# Sheet3.net
KiCad netlist of a schematic drawn in Altium Designer
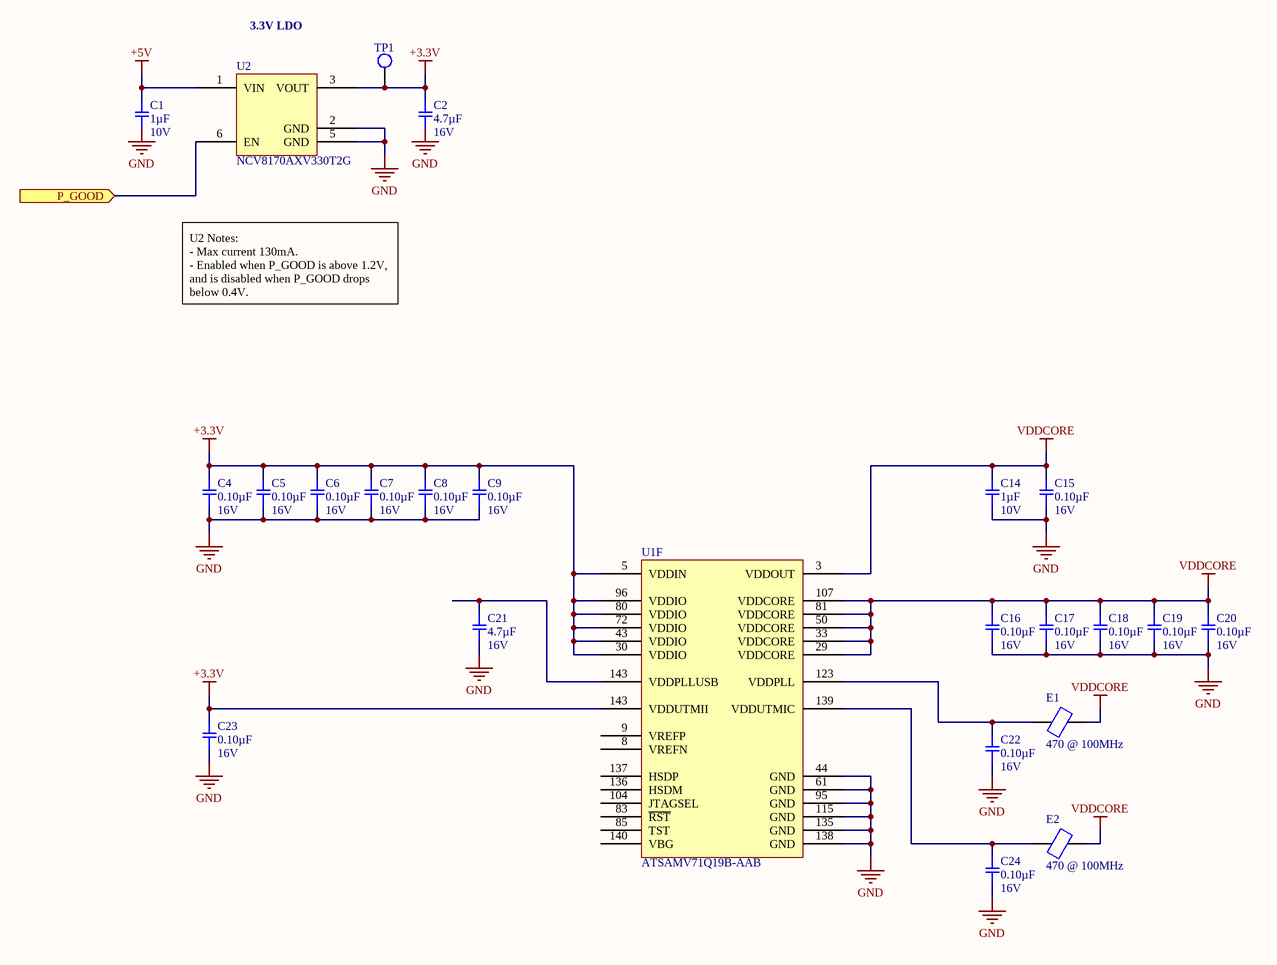
[diagram p0: Sheet3.SchDoc]

(export (version "E")
  (design (tool "Eeschema 10.0.6"))
  (components
    (comp (ref "C1")
      (value "1µF")
      (footprint "SMD-0402C")
      (description "CAP CER 1UF 10V X7S 0402")
      (fields
        (field (name "DIGI-KEY PART NUMBER") "490-13409-1-ND")
        (field (name "PART NUMBER") "GCM155C71A105KE38D")
        (field (name "VOLTAGE") "10V")
      )
      (libsource (lib "capacitor_murata_0402") (part "GCM155C71A105KE38D"))
    )
    (comp (ref "C2")
      (value "4.7µF")
      (footprint "SMD-0805C")
      (description "CAP CER 4.7UF 16V X7R 0805")
      (fields
        (field (name "DIGI-KEY PART NUMBER") "490-10557-1-ND")
        (field (name "PART NUMBER") "GCJ21BR71C475KA01L")
        (field (name "VOLTAGE") "16V")
      )
      (libsource (lib "capacitor_murata_0805") (part "GCJ21BR71C475KA01L"))
    )
    (comp (ref "C4")
      (value "0.10µF")
      (footprint "SMD-0402C")
      (description "CAP CER 0.1UF 16V X7R 0402")
      (fields
        (field (name "DIGI-KEY PART NUMBER") "490-4759-1-ND")
        (field (name "PART NUMBER") "GCM155R71C104KA55D")
        (field (name "VOLTAGE") "16V")
      )
      (libsource (lib "capacitor_murata_0402") (part "GCM155R71C104KA55D"))
    )
    (comp (ref "C5")
      (value "0.10µF")
      (footprint "SMD-0402C")
      (description "CAP CER 0.1UF 16V X7R 0402")
      (fields
        (field (name "DIGI-KEY PART NUMBER") "490-4759-1-ND")
        (field (name "PART NUMBER") "GCM155R71C104KA55D")
        (field (name "VOLTAGE") "16V")
      )
      (libsource (lib "capacitor_murata_0402") (part "GCM155R71C104KA55D"))
    )
    (comp (ref "C6")
      (value "0.10µF")
      (footprint "SMD-0402C")
      (description "CAP CER 0.1UF 16V X7R 0402")
      (fields
        (field (name "DIGI-KEY PART NUMBER") "490-4759-1-ND")
        (field (name "PART NUMBER") "GCM155R71C104KA55D")
        (field (name "VOLTAGE") "16V")
      )
      (libsource (lib "capacitor_murata_0402") (part "GCM155R71C104KA55D"))
    )
    (comp (ref "C7")
      (value "0.10µF")
      (footprint "SMD-0402C")
      (description "CAP CER 0.1UF 16V X7R 0402")
      (fields
        (field (name "DIGI-KEY PART NUMBER") "490-4759-1-ND")
        (field (name "PART NUMBER") "GCM155R71C104KA55D")
        (field (name "VOLTAGE") "16V")
      )
      (libsource (lib "capacitor_murata_0402") (part "GCM155R71C104KA55D"))
    )
    (comp (ref "C8")
      (value "0.10µF")
      (footprint "SMD-0402C")
      (description "CAP CER 0.1UF 16V X7R 0402")
      (fields
        (field (name "DIGI-KEY PART NUMBER") "490-4759-1-ND")
        (field (name "PART NUMBER") "GCM155R71C104KA55D")
        (field (name "VOLTAGE") "16V")
      )
      (libsource (lib "capacitor_murata_0402") (part "GCM155R71C104KA55D"))
    )
    (comp (ref "C9")
      (value "0.10µF")
      (footprint "SMD-0402C")
      (description "CAP CER 0.1UF 16V X7R 0402")
      (fields
        (field (name "DIGI-KEY PART NUMBER") "490-4759-1-ND")
        (field (name "PART NUMBER") "GCM155R71C104KA55D")
        (field (name "VOLTAGE") "16V")
      )
      (libsource (lib "capacitor_murata_0402") (part "GCM155R71C104KA55D"))
    )
    (comp (ref "C14")
      (value "1µF")
      (footprint "SMD-0402C")
      (description "CAP CER 1UF 10V X7S 0402")
      (fields
        (field (name "DIGI-KEY PART NUMBER") "490-13409-1-ND")
        (field (name "PART NUMBER") "GCM155C71A105KE38D")
        (field (name "VOLTAGE") "10V")
      )
      (libsource (lib "capacitor_murata_0402") (part "GCM155C71A105KE38D"))
    )
    (comp (ref "C15")
      (value "0.10µF")
      (footprint "SMD-0402C")
      (description "CAP CER 0.1UF 16V X7R 0402")
      (fields
        (field (name "DIGI-KEY PART NUMBER") "490-4759-1-ND")
        (field (name "PART NUMBER") "GCM155R71C104KA55D")
        (field (name "VOLTAGE") "16V")
      )
      (libsource (lib "capacitor_murata_0402") (part "GCM155R71C104KA55D"))
    )
    (comp (ref "C16")
      (value "0.10µF")
      (footprint "SMD-0402C")
      (description "CAP CER 0.1UF 16V X7R 0402")
      (fields
        (field (name "DIGI-KEY PART NUMBER") "490-4759-1-ND")
        (field (name "PART NUMBER") "GCM155R71C104KA55D")
        (field (name "VOLTAGE") "16V")
      )
      (libsource (lib "capacitor_murata_0402") (part "GCM155R71C104KA55D"))
    )
    (comp (ref "C17")
      (value "0.10µF")
      (footprint "SMD-0402C")
      (description "CAP CER 0.1UF 16V X7R 0402")
      (fields
        (field (name "DIGI-KEY PART NUMBER") "490-4759-1-ND")
        (field (name "PART NUMBER") "GCM155R71C104KA55D")
        (field (name "VOLTAGE") "16V")
      )
      (libsource (lib "capacitor_murata_0402") (part "GCM155R71C104KA55D"))
    )
    (comp (ref "C18")
      (value "0.10µF")
      (footprint "SMD-0402C")
      (description "CAP CER 0.1UF 16V X7R 0402")
      (fields
        (field (name "DIGI-KEY PART NUMBER") "490-4759-1-ND")
        (field (name "PART NUMBER") "GCM155R71C104KA55D")
        (field (name "VOLTAGE") "16V")
      )
      (libsource (lib "capacitor_murata_0402") (part "GCM155R71C104KA55D"))
    )
    (comp (ref "C19")
      (value "0.10µF")
      (footprint "SMD-0402C")
      (description "CAP CER 0.1UF 16V X7R 0402")
      (fields
        (field (name "DIGI-KEY PART NUMBER") "490-4759-1-ND")
        (field (name "PART NUMBER") "GCM155R71C104KA55D")
        (field (name "VOLTAGE") "16V")
      )
      (libsource (lib "capacitor_murata_0402") (part "GCM155R71C104KA55D"))
    )
    (comp (ref "C20")
      (value "0.10µF")
      (footprint "SMD-0402C")
      (description "CAP CER 0.1UF 16V X7R 0402")
      (fields
        (field (name "DIGI-KEY PART NUMBER") "490-4759-1-ND")
        (field (name "PART NUMBER") "GCM155R71C104KA55D")
        (field (name "VOLTAGE") "16V")
      )
      (libsource (lib "capacitor_murata_0402") (part "GCM155R71C104KA55D"))
    )
    (comp (ref "C21")
      (value "4.7µF")
      (footprint "SMD-0805C")
      (description "CAP CER 4.7UF 16V X7R 0805")
      (fields
        (field (name "DIGI-KEY PART NUMBER") "490-10557-1-ND")
        (field (name "PART NUMBER") "GCJ21BR71C475KA01L")
        (field (name "VOLTAGE") "16V")
      )
      (libsource (lib "capacitor_murata_0805") (part "GCJ21BR71C475KA01L"))
    )
    (comp (ref "C22")
      (value "0.10µF")
      (footprint "SMD-0402C")
      (description "CAP CER 0.1UF 16V X7R 0402")
      (fields
        (field (name "DIGI-KEY PART NUMBER") "490-4759-1-ND")
        (field (name "PART NUMBER") "GCM155R71C104KA55D")
        (field (name "VOLTAGE") "16V")
      )
      (libsource (lib "capacitor_murata_0402") (part "GCM155R71C104KA55D"))
    )
    (comp (ref "C23")
      (value "0.10µF")
      (footprint "SMD-0402C")
      (description "CAP CER 0.1UF 16V X7R 0402")
      (fields
        (field (name "DIGI-KEY PART NUMBER") "490-4759-1-ND")
        (field (name "PART NUMBER") "GCM155R71C104KA55D")
        (field (name "VOLTAGE") "16V")
      )
      (libsource (lib "capacitor_murata_0402") (part "GCM155R71C104KA55D"))
    )
    (comp (ref "C24")
      (value "0.10µF")
      (footprint "SMD-0402C")
      (description "CAP CER 0.1UF 16V X7R 0402")
      (fields
        (field (name "DIGI-KEY PART NUMBER") "490-4759-1-ND")
        (field (name "PART NUMBER") "GCM155R71C104KA55D")
        (field (name "VOLTAGE") "16V")
      )
      (libsource (lib "capacitor_murata_0402") (part "GCM155R71C104KA55D"))
    )
    (comp (ref "E1")
      (value "470 @ 100MHz")
      (fields (field (name "Comment") "MPZ1608S471ATD25"))
      (libsource (lib "ModularPayload") (part "MPZ1608S471ATD25"))
    )
    (comp (ref "E2")
      (value "470 @ 100MHz")
      (fields (field (name "Comment") "MPZ1608S471ATD25"))
      (libsource (lib "ModularPayload") (part "MPZ1608S471ATD25"))
    )
    (comp (ref "TP1") (value "TP") (footprint "TP_SMD_40") (libsource (lib "TP") (part "TP")))
    (comp (ref "U1")
      (value "ATSAMV71Q19B-AAB")
      (footprint "TSQFP50P2200X2200X160-144N")
      (libsource (lib "ModularPayload") (part "ATSAMV71Q19B-AAB"))
    )
    (comp (ref "U2")
      (value "NCV8170AXV330T2G")
      (footprint "SOTFL50P160X60-6N")
      (libsource (lib "ModularPayload") (part "NCV8170AXV330T2G"))
    )
  )
  (nets
    (net (code "1") (name "+3.3V") (class "Default")
      (node (ref "C2") (pin "2") (pinfunction "2_2") (pintype "passive"))
      (node (ref "C23") (pin "2") (pinfunction "2_2") (pintype "passive"))
      (node (ref "C4") (pin "2") (pinfunction "2_2") (pintype "passive"))
      (node (ref "C5") (pin "2") (pinfunction "2_2") (pintype "passive"))
      (node (ref "C6") (pin "2") (pinfunction "2_2") (pintype "passive"))
      (node (ref "C7") (pin "2") (pinfunction "2_2") (pintype "passive"))
      (node (ref "C8") (pin "2") (pinfunction "2_2") (pintype "passive"))
      (node (ref "C9") (pin "2") (pinfunction "2_2") (pintype "passive"))
      (node (ref "TP1") (pin "1") (pintype "passive"))
      (node (ref "U1") (pin "143") (pinfunction "VDDUTMII_143") (pintype "passive"))
      (node (ref "U1") (pin "30") (pinfunction "VDDIO_30") (pintype "passive"))
      (node (ref "U1") (pin "43") (pinfunction "VDDIO_43") (pintype "passive"))
      (node (ref "U1") (pin "5") (pinfunction "VDDIN_5") (pintype "passive"))
      (node (ref "U1") (pin "72") (pinfunction "VDDIO_72") (pintype "passive"))
      (node (ref "U1") (pin "80") (pinfunction "VDDIO_80") (pintype "passive"))
      (node (ref "U1") (pin "96") (pinfunction "VDDIO_96") (pintype "passive"))
      (node (ref "U2") (pin "3") (pinfunction "VOUT_3") (pintype "passive"))
    )
    (net (code "2") (name "+5V") (class "Default")
      (node (ref "C1") (pin "2") (pinfunction "2_2") (pintype "passive"))
      (node (ref "U2") (pin "1") (pinfunction "VIN_1") (pintype "passive"))
    )
    (net (code "3") (name "/P_GOOD") (class "Default")
      (node (ref "U2") (pin "6") (pinfunction "EN_6") (pintype "passive"))
    )
    (net (code "4") (name "GND") (class "Default")
      (node (ref "C1") (pin "1") (pinfunction "1_1") (pintype "passive"))
      (node (ref "C14") (pin "1") (pinfunction "1_1") (pintype "passive"))
      (node (ref "C15") (pin "1") (pinfunction "1_1") (pintype "passive"))
      (node (ref "C16") (pin "1") (pinfunction "1_1") (pintype "passive"))
      (node (ref "C17") (pin "1") (pinfunction "1_1") (pintype "passive"))
      (node (ref "C18") (pin "1") (pinfunction "1_1") (pintype "passive"))
      (node (ref "C19") (pin "1") (pinfunction "1_1") (pintype "passive"))
      (node (ref "C2") (pin "1") (pinfunction "1_1") (pintype "passive"))
      (node (ref "C20") (pin "1") (pinfunction "1_1") (pintype "passive"))
      (node (ref "C21") (pin "1") (pinfunction "1_1") (pintype "passive"))
      (node (ref "C22") (pin "1") (pinfunction "1_1") (pintype "passive"))
      (node (ref "C23") (pin "1") (pinfunction "1_1") (pintype "passive"))
      (node (ref "C24") (pin "1") (pinfunction "1_1") (pintype "passive"))
      (node (ref "C4") (pin "1") (pinfunction "1_1") (pintype "passive"))
      (node (ref "C5") (pin "1") (pinfunction "1_1") (pintype "passive"))
      (node (ref "C6") (pin "1") (pinfunction "1_1") (pintype "passive"))
      (node (ref "C7") (pin "1") (pinfunction "1_1") (pintype "passive"))
      (node (ref "C8") (pin "1") (pinfunction "1_1") (pintype "passive"))
      (node (ref "C9") (pin "1") (pinfunction "1_1") (pintype "passive"))
      (node (ref "U1") (pin "115") (pinfunction "GND_115") (pintype "passive"))
      (node (ref "U1") (pin "135") (pinfunction "GND_135") (pintype "passive"))
      (node (ref "U1") (pin "138") (pinfunction "GND_138") (pintype "passive"))
      (node (ref "U1") (pin "44") (pinfunction "GND_44") (pintype "passive"))
      (node (ref "U1") (pin "61") (pinfunction "GND_61") (pintype "passive"))
      (node (ref "U1") (pin "95") (pinfunction "GND_95") (pintype "passive"))
      (node (ref "U2") (pin "2") (pinfunction "GND_2") (pintype "passive"))
      (node (ref "U2") (pin "5") (pinfunction "GND_5") (pintype "passive"))
    )
    (net (code "5") (name "Net-(U1F-VDDPLL)") (class "Default")
      (node (ref "C22") (pin "2") (pinfunction "2_2") (pintype "passive"))
      (node (ref "E1") (pin "1") (pinfunction "1_1") (pintype "passive"))
      (node (ref "U1") (pin "123") (pinfunction "VDDPLL_123") (pintype "passive"))
    )
    (net (code "6") (name "Net-(U1F-VDDPLLUSB)") (class "Default")
      (node (ref "C21") (pin "2") (pinfunction "2_2") (pintype "passive"))
      (node (ref "U1") (pin "143") (pinfunction "VDDPLLUSB_143") (pintype "passive"))
    )
    (net (code "7") (name "Net-(U1F-VDDUTMIC)") (class "Default")
      (node (ref "C24") (pin "2") (pinfunction "2_2") (pintype "passive"))
      (node (ref "E2") (pin "1") (pinfunction "1_1") (pintype "passive"))
      (node (ref "U1") (pin "139") (pinfunction "VDDUTMIC_139") (pintype "passive"))
    )
    (net (code "8") (name "VDDCORE") (class "Default")
      (node (ref "C14") (pin "2") (pinfunction "2_2") (pintype "passive"))
      (node (ref "C15") (pin "2") (pinfunction "2_2") (pintype "passive"))
      (node (ref "C16") (pin "2") (pinfunction "2_2") (pintype "passive"))
      (node (ref "C17") (pin "2") (pinfunction "2_2") (pintype "passive"))
      (node (ref "C18") (pin "2") (pinfunction "2_2") (pintype "passive"))
      (node (ref "C19") (pin "2") (pinfunction "2_2") (pintype "passive"))
      (node (ref "C20") (pin "2") (pinfunction "2_2") (pintype "passive"))
      (node (ref "E1") (pin "2") (pinfunction "2_2") (pintype "passive"))
      (node (ref "E2") (pin "2") (pinfunction "2_2") (pintype "passive"))
      (node (ref "U1") (pin "107") (pinfunction "VDDCORE_107") (pintype "passive"))
      (node (ref "U1") (pin "29") (pinfunction "VDDCORE_29") (pintype "passive"))
      (node (ref "U1") (pin "3") (pinfunction "VDDOUT_3") (pintype "passive"))
      (node (ref "U1") (pin "33") (pinfunction "VDDCORE_33") (pintype "passive"))
      (node (ref "U1") (pin "50") (pinfunction "VDDCORE_50") (pintype "passive"))
      (node (ref "U1") (pin "81") (pinfunction "VDDCORE_81") (pintype "passive"))
    )
    (net (code "9") (name "unconnected-(U1F-HSDM-Pad136)") (class "Default")
      (node (ref "U1") (pin "136") (pinfunction "HSDM_136") (pintype "passive"))
    )
    (net (code "10") (name "unconnected-(U1F-HSDP-Pad137)") (class "Default")
      (node (ref "U1") (pin "137") (pinfunction "HSDP_137") (pintype "passive"))
    )
    (net (code "11") (name "unconnected-(U1F-JTAGSEL-Pad104)") (class "Default")
      (node (ref "U1") (pin "104") (pinfunction "JTAGSEL_104") (pintype "passive"))
    )
    (net (code "12") (name "unconnected-(U1F-TST-Pad85)") (class "Default")
      (node (ref "U1") (pin "85") (pinfunction "TST_85") (pintype "passive"))
    )
    (net (code "13") (name "unconnected-(U1F-VBG-Pad140)") (class "Default")
      (node (ref "U1") (pin "140") (pinfunction "VBG_140") (pintype "passive"))
    )
    (net (code "14") (name "unconnected-(U1F-VREFN-Pad8)") (class "Default")
      (node (ref "U1") (pin "8") (pinfunction "VREFN_8") (pintype "passive"))
    )
    (net (code "15") (name "unconnected-(U1F-VREFP-Pad9)") (class "Default")
      (node (ref "U1") (pin "9") (pinfunction "VREFP_9") (pintype "passive"))
    )
    (net (code "16") (name "unconnected-(U1F-~{RST}-Pad83)") (class "Default")
      (node (ref "U1") (pin "83") (pinfunction "~{RST}_83") (pintype "passive"))
    )
  )
)
